# Sheet1.net
KiCad netlist of a schematic drawn in Altium Designer
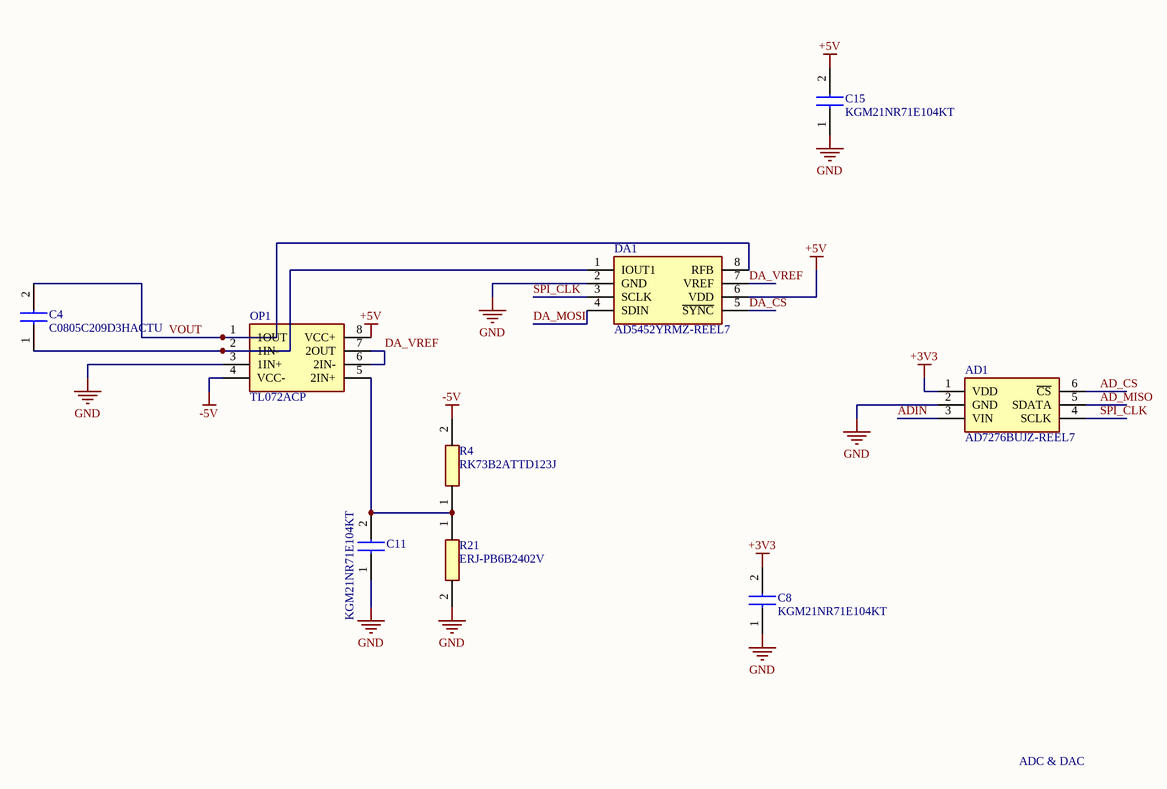
[diagram p0: Sheet1.SchDoc]

(export (version "E")
  (design (tool "Eeschema 10.0.6"))
  (components
    (comp (ref "AD1")
      (value "AD7276BUJZ-REEL7")
      (footprint "SamacSys:SOT95P280X100-6N")
      (description "Integrated Circuit")
      (libsource (lib "*") (part "AD7276BUJZ-REEL7"))
    )
    (comp (ref "C4")
      (value "C0805C209D3HACTU")
      (footprint "SamacSys:C0805")
      (description "Capacitor")
      (libsource (lib "*") (part "C0805C209D3HACTU"))
    )
    (comp (ref "C8")
      (value "KGM21NR71E104KT")
      (footprint "SamacSys:CAPC2012X100N")
      (description "Capacitor")
      (fields (field (name "MOUSER PART NUMBER") "581-KGM21NR71E104KT"))
      (libsource (lib "*") (part "KGM21NR71E104KT"))
    )
    (comp (ref "C11")
      (value "KGM21NR71E104KT")
      (footprint "SamacSys:CAPC2012X100N")
      (description "Capacitor")
      (fields (field (name "MOUSER PART NUMBER") "581-KGM21NR71E104KT"))
      (libsource (lib "*") (part "KGM21NR71E104KT"))
    )
    (comp (ref "C15")
      (value "KGM21NR71E104KT")
      (footprint "SamacSys:CAPC2012X100N")
      (description "Capacitor")
      (fields (field (name "MOUSER PART NUMBER") "581-KGM21NR71E104KT"))
      (libsource (lib "*") (part "KGM21NR71E104KT"))
    )
    (comp (ref "DA1")
      (value "AD5452YRMZ-REEL7")
      (footprint "SamacSys:SOP65P490X110-8N")
      (description "Integrated Circuit")
      (fields (field (name "MOUSER PART NUMBER") "584-AD5452YRMZ-R7"))
      (libsource (lib "SamacSys") (part "AD5452YRMZ-REEL7"))
    )
    (comp (ref "OP1")
      (value "TL072ACP")
      (footprint "SamacSys:DIP794W53P254L959H508Q8N")
      (description "Integrated Circuit")
      (fields (field (name "MOUSER PART NUMBER") "595-TL072ACP"))
      (libsource (lib "*") (part "TL072ACP"))
    )
    (comp (ref "R4")
      (value "RK73B2ATTD123J")
      (footprint "SamacSys:RESC2012X60N")
      (description "Resistor")
      (libsource (lib "*") (part "RK73B2ATTD123J"))
    )
    (comp (ref "R21")
      (value "ERJ-PB6B2402V")
      (footprint "SamacSys:RESC2012X70N")
      (description "Resistor")
      (fields (field (name "MOUSER PART NUMBER") "667-ERJ-PB6B2402V"))
      (libsource (lib "*") (part "ERJ-PB6B2402V"))
    )
  )
  (nets
    (net (code "1") (name "+3V3") (class "Default")
      (node (ref "AD1") (pin "1") (pinfunction "VDD_1") (pintype "passive"))
      (node (ref "C8") (pin "2") (pinfunction "2_2") (pintype "passive"))
    )
    (net (code "2") (name "+5V") (class "Default")
      (node (ref "C15") (pin "2") (pinfunction "2_2") (pintype "passive"))
      (node (ref "DA1") (pin "6") (pinfunction "VDD_6") (pintype "passive"))
      (node (ref "OP1") (pin "8") (pinfunction "VCC+_8") (pintype "passive"))
    )
    (net (code "3") (name "-5V") (class "Default")
      (node (ref "OP1") (pin "4") (pinfunction "VCC-_4") (pintype "passive"))
      (node (ref "R4") (pin "2") (pinfunction "2_2") (pintype "passive"))
    )
    (net (code "4") (name "/ADIN") (class "Default")
      (node (ref "AD1") (pin "3") (pinfunction "VIN_3") (pintype "passive"))
    )
    (net (code "5") (name "/AD_CS") (class "Default")
      (node (ref "AD1") (pin "6") (pinfunction "~{CS}_6") (pintype "passive"))
    )
    (net (code "6") (name "/AD_MISO") (class "Default")
      (node (ref "AD1") (pin "5") (pinfunction "SDATA_5") (pintype "passive"))
    )
    (net (code "7") (name "/DA_CS") (class "Default")
      (node (ref "DA1") (pin "5") (pinfunction "~{SYNC}_5") (pintype "passive"))
    )
    (net (code "8") (name "/DA_MOSI") (class "Default")
      (node (ref "DA1") (pin "4") (pinfunction "SDIN_4") (pintype "passive"))
    )
    (net (code "9") (name "/DA_VREF") (class "Default")
      (node (ref "DA1") (pin "7") (pinfunction "VREF_7") (pintype "passive"))
      (node (ref "OP1") (pin "6") (pinfunction "2IN-_6") (pintype "passive"))
      (node (ref "OP1") (pin "7") (pinfunction "2OUT_7") (pintype "passive"))
    )
    (net (code "10") (name "/SPI_CLK") (class "Default")
      (node (ref "AD1") (pin "4") (pinfunction "SCLK_4") (pintype "passive"))
      (node (ref "DA1") (pin "3") (pinfunction "SCLK_3") (pintype "passive"))
    )
    (net (code "11") (name "/VOUT") (class "Default")
      (node (ref "C4") (pin "2") (pinfunction "2_2") (pintype "passive"))
      (node (ref "DA1") (pin "8") (pinfunction "RFB_8") (pintype "passive"))
      (node (ref "OP1") (pin "1") (pinfunction "1OUT_1") (pintype "passive"))
    )
    (net (code "12") (name "GND") (class "Default")
      (node (ref "AD1") (pin "2") (pinfunction "GND_2") (pintype "passive"))
      (node (ref "C11") (pin "1") (pinfunction "1_1") (pintype "passive"))
      (node (ref "C15") (pin "1") (pinfunction "1_1") (pintype "passive"))
      (node (ref "C8") (pin "1") (pinfunction "1_1") (pintype "passive"))
      (node (ref "DA1") (pin "2") (pinfunction "GND_2") (pintype "passive"))
      (node (ref "OP1") (pin "3") (pinfunction "1IN+_3") (pintype "passive"))
      (node (ref "R21") (pin "2") (pinfunction "2_2") (pintype "passive"))
    )
    (net (code "13") (name "Net-(DA1-IOUT1)") (class "Default")
      (node (ref "C4") (pin "1") (pinfunction "1_1") (pintype "passive"))
      (node (ref "DA1") (pin "1") (pinfunction "IOUT1_1") (pintype "passive"))
      (node (ref "OP1") (pin "2") (pinfunction "1IN-_2") (pintype "passive"))
    )
    (net (code "14") (name "Net-(OP1-2IN+)") (class "Default")
      (node (ref "C11") (pin "2") (pinfunction "2_2") (pintype "passive"))
      (node (ref "OP1") (pin "5") (pinfunction "2IN+_5") (pintype "passive"))
      (node (ref "R21") (pin "1") (pinfunction "1_1") (pintype "passive"))
      (node (ref "R4") (pin "1") (pinfunction "1_1") (pintype "passive"))
    )
  )
)
